# switch_hat_v3.net
KiCad netlist of a schematic drawn in EAGLE
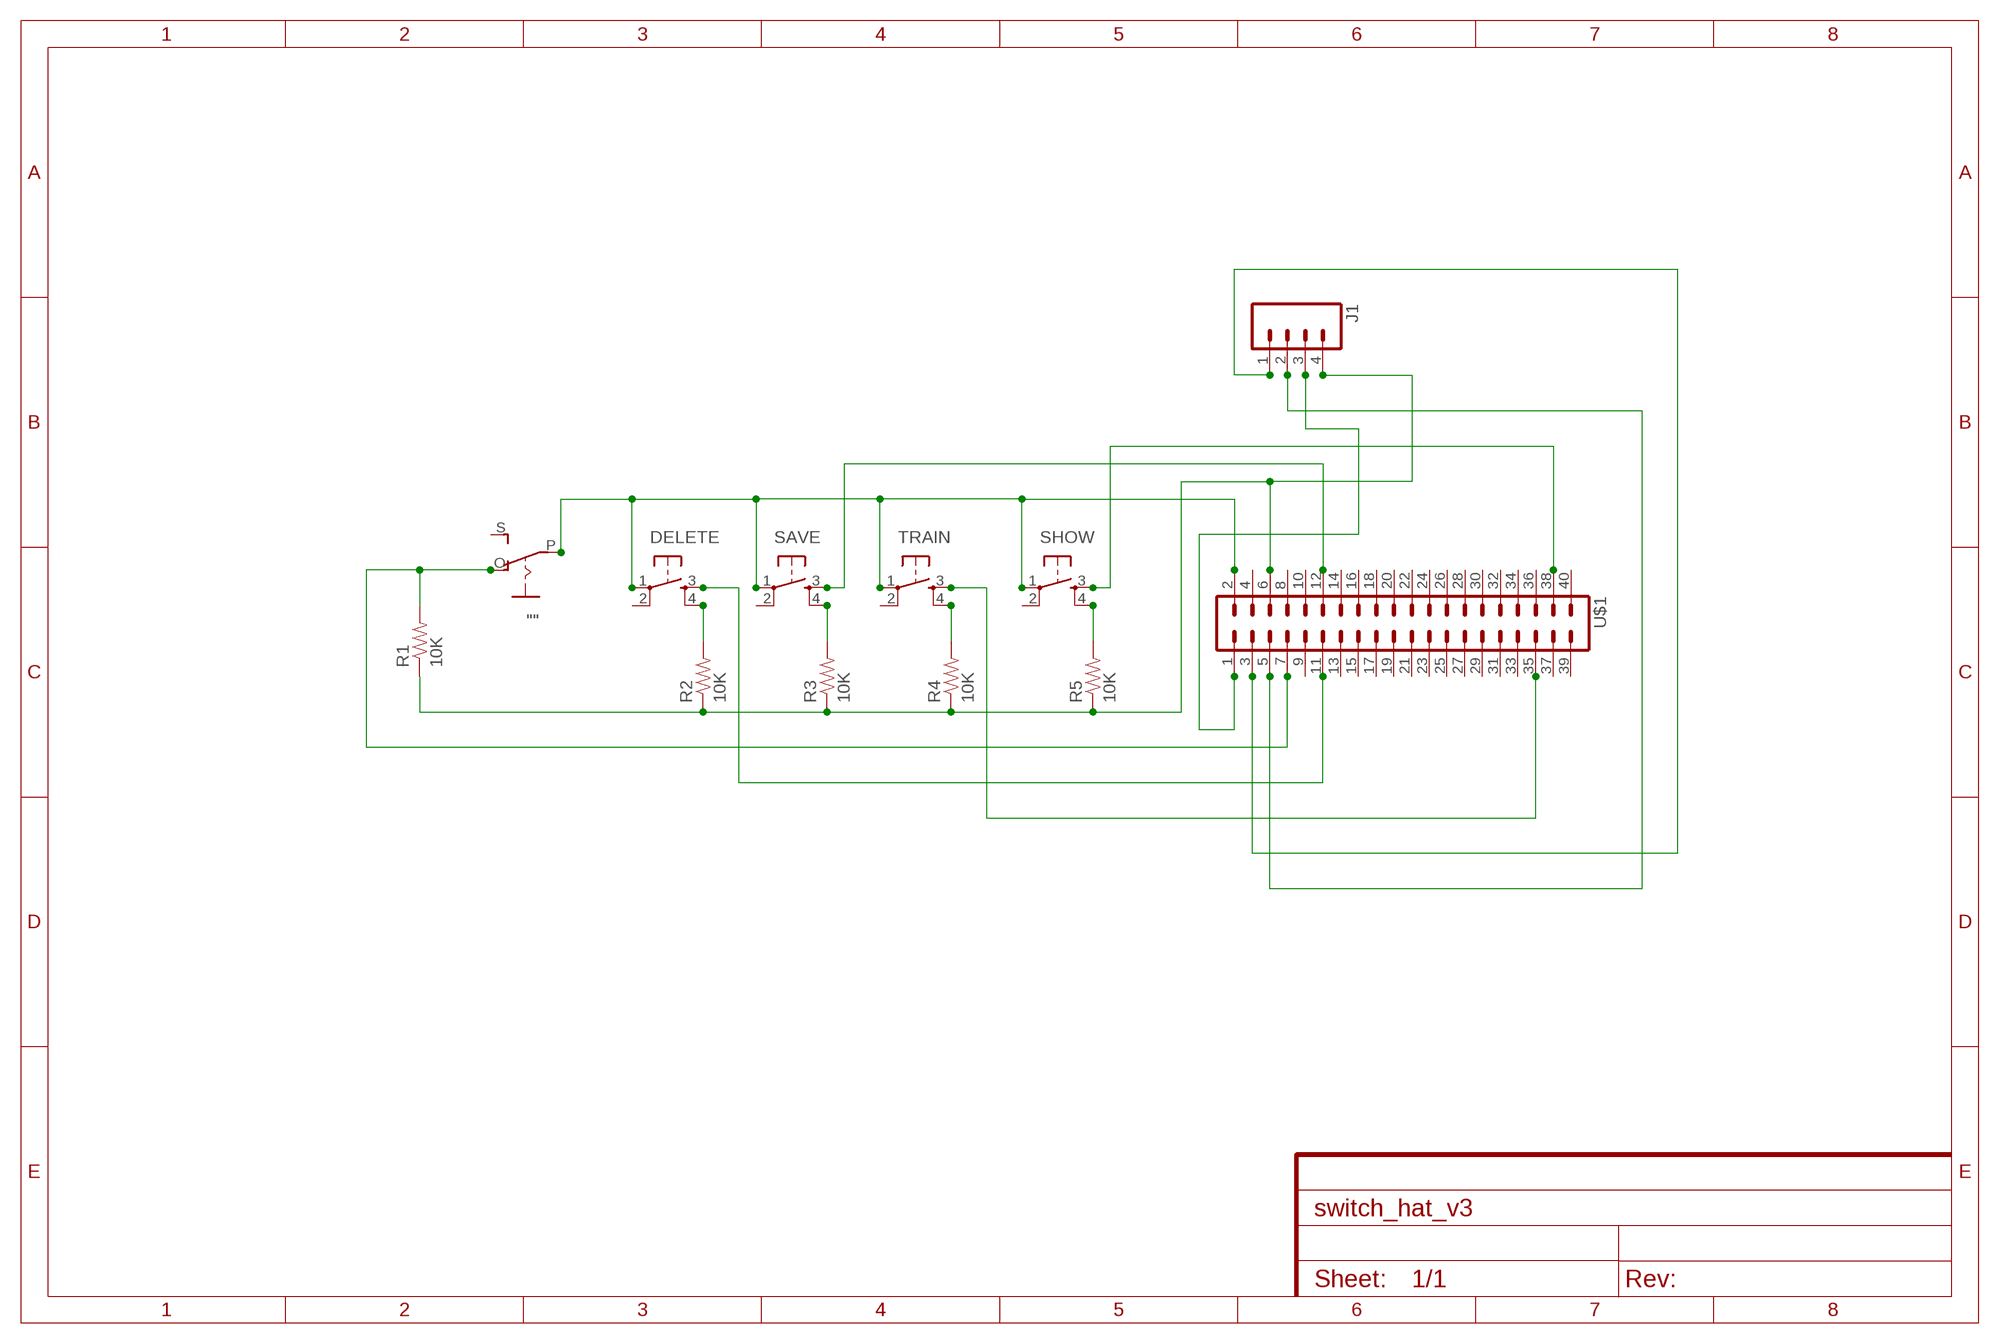
[diagram p0: schematic, sheet 1]

(export (version "E")
  (design (tool "Eeschema 10.0.6"))
  (components
    (comp (ref "\"\"")
      (value "EG1218S")
      (footprint "eagle-import:EG1218")
      (libsource (lib "eagle-import") (part "EG1218S"))
    )
    (comp (ref "DELETE")
      (value "TAC_SWITCHPTH")
      (footprint "eagle-import:TACTILE-PTH")
      (libsource (lib "eagle-import") (part "TAC_SWITCHPTH"))
    )
    (comp (ref "J1")
      (value "M04LOCK")
      (footprint "eagle-import:1X04_LOCK")
      (libsource (lib "eagle-import") (part "M04LOCK"))
    )
    (comp (ref "R1")
      (value "10K")
      (footprint "eagle-import:0805")
      (libsource (lib "eagle-import") (part "RESISTOR0805-RES"))
    )
    (comp (ref "R2")
      (value "10K")
      (footprint "eagle-import:0805")
      (libsource (lib "eagle-import") (part "RESISTOR0805-RES"))
    )
    (comp (ref "R3")
      (value "10K")
      (footprint "eagle-import:0805")
      (libsource (lib "eagle-import") (part "RESISTOR0805-RES"))
    )
    (comp (ref "R4")
      (value "10K")
      (footprint "eagle-import:0805")
      (libsource (lib "eagle-import") (part "RESISTOR0805-RES"))
    )
    (comp (ref "R5")
      (value "10K")
      (footprint "eagle-import:0805")
      (libsource (lib "eagle-import") (part "RESISTOR0805-RES"))
    )
    (comp (ref "SAVE")
      (value "TAC_SWITCHPTH")
      (footprint "eagle-import:TACTILE-PTH")
      (libsource (lib "eagle-import") (part "TAC_SWITCHPTH"))
    )
    (comp (ref "SHOW")
      (value "TAC_SWITCHPTH")
      (footprint "eagle-import:TACTILE-PTH")
      (libsource (lib "eagle-import") (part "TAC_SWITCHPTH"))
    )
    (comp (ref "TRAIN")
      (value "TAC_SWITCHPTH")
      (footprint "eagle-import:TACTILE-PTH")
      (libsource (lib "eagle-import") (part "TAC_SWITCHPTH"))
    )
    (comp (ref "U$1")
      (value "PIZERO_THROUGH_HOLE")
      (footprint "eagle-import:PIZERO_THOUGH_HOLE")
      (libsource (lib "eagle-import") (part "PIZERO_THROUGH_HOLE"))
    )
  )
  (nets
    (net (code "1") (name "Net-(\"\"-PadO)") (class "Default")
      (node (ref "\"\"") (pin "O") (pinfunction "O_O") (pintype "passive"))
      (node (ref "R1") (pin "2") (pinfunction "2_2") (pintype "passive"))
      (node (ref "U$1") (pin "7") (pinfunction "7_7") (pintype "passive"))
    )
    (net (code "2") (name "Net-(\"\"-PadP)") (class "Default")
      (node (ref "\"\"") (pin "P") (pinfunction "P_P") (pintype "passive"))
      (node (ref "DELETE") (pin "1") (pinfunction "1_1") (pintype "passive"))
      (node (ref "SAVE") (pin "1") (pinfunction "1_1") (pintype "passive"))
      (node (ref "SHOW") (pin "1") (pinfunction "1_1") (pintype "passive"))
      (node (ref "TRAIN") (pin "1") (pinfunction "1_1") (pintype "passive"))
      (node (ref "U$1") (pin "2") (pinfunction "2_2") (pintype "passive"))
    )
    (net (code "3") (name "Net-(DELETE-Pad3)") (class "Default")
      (node (ref "DELETE") (pin "3") (pinfunction "3_3") (pintype "passive"))
      (node (ref "U$1") (pin "11") (pinfunction "11_11") (pintype "passive"))
    )
    (net (code "4") (name "Net-(DELETE-Pad4)") (class "Default")
      (node (ref "DELETE") (pin "4") (pinfunction "4_4") (pintype "passive"))
      (node (ref "R2") (pin "2") (pinfunction "2_2") (pintype "passive"))
    )
    (net (code "5") (name "Net-(J1-Pad1)") (class "Default")
      (node (ref "J1") (pin "1") (pinfunction "1_1") (pintype "passive"))
      (node (ref "U$1") (pin "3") (pinfunction "3_3") (pintype "passive"))
    )
    (net (code "6") (name "Net-(J1-Pad2)") (class "Default")
      (node (ref "J1") (pin "2") (pinfunction "2_2") (pintype "passive"))
      (node (ref "U$1") (pin "5") (pinfunction "5_5") (pintype "passive"))
    )
    (net (code "7") (name "Net-(J1-Pad3)") (class "Default")
      (node (ref "J1") (pin "3") (pinfunction "3_3") (pintype "passive"))
      (node (ref "U$1") (pin "1") (pinfunction "1_1") (pintype "passive"))
    )
    (net (code "8") (name "Net-(J1-Pad4)") (class "Default")
      (node (ref "J1") (pin "4") (pinfunction "4_4") (pintype "passive"))
      (node (ref "R1") (pin "1") (pinfunction "1_1") (pintype "passive"))
      (node (ref "R2") (pin "1") (pinfunction "1_1") (pintype "passive"))
      (node (ref "R3") (pin "1") (pinfunction "1_1") (pintype "passive"))
      (node (ref "R4") (pin "1") (pinfunction "1_1") (pintype "passive"))
      (node (ref "R5") (pin "1") (pinfunction "1_1") (pintype "passive"))
      (node (ref "U$1") (pin "6") (pinfunction "6_6") (pintype "passive"))
    )
    (net (code "9") (name "Net-(R3-Pad2)") (class "Default")
      (node (ref "R3") (pin "2") (pinfunction "2_2") (pintype "passive"))
      (node (ref "SAVE") (pin "4") (pinfunction "4_4") (pintype "passive"))
    )
    (net (code "10") (name "Net-(R4-Pad2)") (class "Default")
      (node (ref "R4") (pin "2") (pinfunction "2_2") (pintype "passive"))
      (node (ref "TRAIN") (pin "4") (pinfunction "4_4") (pintype "passive"))
    )
    (net (code "11") (name "Net-(R5-Pad2)") (class "Default")
      (node (ref "R5") (pin "2") (pinfunction "2_2") (pintype "passive"))
      (node (ref "SHOW") (pin "4") (pinfunction "4_4") (pintype "passive"))
    )
    (net (code "12") (name "Net-(SAVE-Pad3)") (class "Default")
      (node (ref "SAVE") (pin "3") (pinfunction "3_3") (pintype "passive"))
      (node (ref "U$1") (pin "12") (pinfunction "12_12") (pintype "passive"))
    )
    (net (code "13") (name "Net-(SHOW-Pad3)") (class "Default")
      (node (ref "SHOW") (pin "3") (pinfunction "3_3") (pintype "passive"))
      (node (ref "U$1") (pin "38") (pinfunction "38_38") (pintype "passive"))
    )
    (net (code "14") (name "Net-(TRAIN-Pad3)") (class "Default")
      (node (ref "TRAIN") (pin "3") (pinfunction "3_3") (pintype "passive"))
      (node (ref "U$1") (pin "35") (pinfunction "35_35") (pintype "passive"))
    )
    (net (code "15") (name "unconnected-(\"\"-PadS)") (class "Default")
      (node (ref "\"\"") (pin "S") (pinfunction "S_S") (pintype "passive"))
    )
    (net (code "16") (name "unconnected-(DELETE-Pad2)") (class "Default")
      (node (ref "DELETE") (pin "2") (pinfunction "2_2") (pintype "passive"))
    )
    (net (code "17") (name "unconnected-(SAVE-Pad2)") (class "Default")
      (node (ref "SAVE") (pin "2") (pinfunction "2_2") (pintype "passive"))
    )
    (net (code "18") (name "unconnected-(SHOW-Pad2)") (class "Default")
      (node (ref "SHOW") (pin "2") (pinfunction "2_2") (pintype "passive"))
    )
    (net (code "19") (name "unconnected-(TRAIN-Pad2)") (class "Default")
      (node (ref "TRAIN") (pin "2") (pinfunction "2_2") (pintype "passive"))
    )
    (net (code "20") (name "unconnected-(U$1-Pad4)") (class "Default")
      (node (ref "U$1") (pin "4") (pinfunction "4_4") (pintype "passive"))
    )
    (net (code "21") (name "unconnected-(U$1-Pad8)") (class "Default")
      (node (ref "U$1") (pin "8") (pinfunction "8_8") (pintype "passive"))
    )
    (net (code "22") (name "unconnected-(U$1-Pad9)") (class "Default")
      (node (ref "U$1") (pin "9") (pinfunction "9_9") (pintype "passive"))
    )
    (net (code "23") (name "unconnected-(U$1-Pad10)") (class "Default")
      (node (ref "U$1") (pin "10") (pinfunction "10_10") (pintype "passive"))
    )
    (net (code "24") (name "unconnected-(U$1-Pad13)") (class "Default")
      (node (ref "U$1") (pin "13") (pinfunction "13_13") (pintype "passive"))
    )
    (net (code "25") (name "unconnected-(U$1-Pad14)") (class "Default")
      (node (ref "U$1") (pin "14") (pinfunction "14_14") (pintype "passive"))
    )
    (net (code "26") (name "unconnected-(U$1-Pad15)") (class "Default")
      (node (ref "U$1") (pin "15") (pinfunction "15_15") (pintype "passive"))
    )
    (net (code "27") (name "unconnected-(U$1-Pad16)") (class "Default")
      (node (ref "U$1") (pin "16") (pinfunction "16_16") (pintype "passive"))
    )
    (net (code "28") (name "unconnected-(U$1-Pad17)") (class "Default")
      (node (ref "U$1") (pin "17") (pinfunction "17_17") (pintype "passive"))
    )
    (net (code "29") (name "unconnected-(U$1-Pad18)") (class "Default")
      (node (ref "U$1") (pin "18") (pinfunction "18_18") (pintype "passive"))
    )
    (net (code "30") (name "unconnected-(U$1-Pad19)") (class "Default")
      (node (ref "U$1") (pin "19") (pinfunction "19_19") (pintype "passive"))
    )
    (net (code "31") (name "unconnected-(U$1-Pad20)") (class "Default")
      (node (ref "U$1") (pin "20") (pinfunction "20_20") (pintype "passive"))
    )
    (net (code "32") (name "unconnected-(U$1-Pad21)") (class "Default")
      (node (ref "U$1") (pin "21") (pinfunction "21_21") (pintype "passive"))
    )
    (net (code "33") (name "unconnected-(U$1-Pad22)") (class "Default")
      (node (ref "U$1") (pin "22") (pinfunction "22_22") (pintype "passive"))
    )
    (net (code "34") (name "unconnected-(U$1-Pad23)") (class "Default")
      (node (ref "U$1") (pin "23") (pinfunction "23_23") (pintype "passive"))
    )
    (net (code "35") (name "unconnected-(U$1-Pad24)") (class "Default")
      (node (ref "U$1") (pin "24") (pinfunction "24_24") (pintype "passive"))
    )
    (net (code "36") (name "unconnected-(U$1-Pad25)") (class "Default")
      (node (ref "U$1") (pin "25") (pinfunction "25_25") (pintype "passive"))
    )
    (net (code "37") (name "unconnected-(U$1-Pad26)") (class "Default")
      (node (ref "U$1") (pin "26") (pinfunction "26_26") (pintype "passive"))
    )
    (net (code "38") (name "unconnected-(U$1-Pad27)") (class "Default")
      (node (ref "U$1") (pin "27") (pinfunction "27_27") (pintype "passive"))
    )
    (net (code "39") (name "unconnected-(U$1-Pad28)") (class "Default")
      (node (ref "U$1") (pin "28") (pinfunction "28_28") (pintype "passive"))
    )
    (net (code "40") (name "unconnected-(U$1-Pad29)") (class "Default")
      (node (ref "U$1") (pin "29") (pinfunction "29_29") (pintype "passive"))
    )
    (net (code "41") (name "unconnected-(U$1-Pad30)") (class "Default")
      (node (ref "U$1") (pin "30") (pinfunction "30_30") (pintype "passive"))
    )
    (net (code "42") (name "unconnected-(U$1-Pad31)") (class "Default")
      (node (ref "U$1") (pin "31") (pinfunction "31_31") (pintype "passive"))
    )
    (net (code "43") (name "unconnected-(U$1-Pad32)") (class "Default")
      (node (ref "U$1") (pin "32") (pinfunction "32_32") (pintype "passive"))
    )
    (net (code "44") (name "unconnected-(U$1-Pad33)") (class "Default")
      (node (ref "U$1") (pin "33") (pinfunction "33_33") (pintype "passive"))
    )
    (net (code "45") (name "unconnected-(U$1-Pad34)") (class "Default")
      (node (ref "U$1") (pin "34") (pinfunction "34_34") (pintype "passive"))
    )
    (net (code "46") (name "unconnected-(U$1-Pad36)") (class "Default")
      (node (ref "U$1") (pin "36") (pinfunction "36_36") (pintype "passive"))
    )
    (net (code "47") (name "unconnected-(U$1-Pad37)") (class "Default")
      (node (ref "U$1") (pin "37") (pinfunction "37_37") (pintype "passive"))
    )
    (net (code "48") (name "unconnected-(U$1-Pad39)") (class "Default")
      (node (ref "U$1") (pin "39") (pinfunction "39_39") (pintype "passive"))
    )
    (net (code "49") (name "unconnected-(U$1-Pad40)") (class "Default")
      (node (ref "U$1") (pin "40") (pinfunction "40_40") (pintype "passive"))
    )
  )
)
